# PWR_TLV71318.net
KiCad netlist of a schematic drawn in Altium Designer
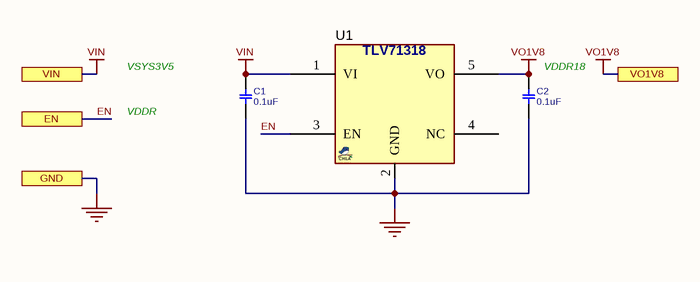
[diagram p0: PWR_TLV71318.SchDoc]

(export (version "E")
  (design (tool "Eeschema 10.0.6"))
  (components
    (comp (ref "C1")
      (value "0.1uF")
      (footprint "C0402")
      (description "CAP, MLCC")
      (fields (field (name "MANF_P#") "GRM155R61E104") (field (name "MANF") "Murata"))
      (libsource (lib "passive_smd") (part "CAP_SMD_MLCC"))
    )
    (comp (ref "C2")
      (value "0.1uF")
      (footprint "C0402")
      (description "CAP, MLCC")
      (fields (field (name "MANF_P#") "GRM155R61E104") (field (name "MANF") "Murata"))
      (libsource (lib "passive_smd") (part "CAP_SMD_MLCC"))
    )
    (comp (ref "U1")
      (value "TLV71318")
      (footprint "SOT23_5")
      (description "REG, Linear, LDO0.23V, 0.15A, 1.4~-5.5VIN, SOT23-5")
      (fields (field (name "MANF") "Texas Instruments") (field (name "MANF_P#") "TLV71318PDBV"))
      (libsource (lib "pwr_reg_linear_LDO_highPSRR") (part "VREG_TLV71318_SOT23"))
    )
  )
  (nets
    (net (code "1") (name "/EN") (class "Default")
      (node (ref "U1") (pin "3") (pinfunction "EN_3") (pintype "passive"))
    )
    (net (code "2") (name "GND") (class "Default")
      (node (ref "C1") (pin "1") (pinfunction "1_1") (pintype "passive"))
      (node (ref "C2") (pin "1") (pinfunction "1_1") (pintype "passive"))
      (node (ref "U1") (pin "2") (pinfunction "GND_2") (pintype "passive"))
    )
    (net (code "3") (name "VIN") (class "Default")
      (node (ref "C1") (pin "2") (pinfunction "2_2") (pintype "passive"))
      (node (ref "U1") (pin "1") (pinfunction "VI_1") (pintype "passive"))
    )
    (net (code "4") (name "VO1V8") (class "Default")
      (node (ref "C2") (pin "2") (pinfunction "2_2") (pintype "passive"))
      (node (ref "U1") (pin "5") (pinfunction "VO_5") (pintype "passive"))
    )
    (net (code "5") (name "unconnected-(U1-NC-Pad4)") (class "Default")
      (node (ref "U1") (pin "4") (pinfunction "NC_4") (pintype "passive"))
    )
  )
)
